# voltagetransfer.net
KiCad netlist of a schematic drawn in EAGLE
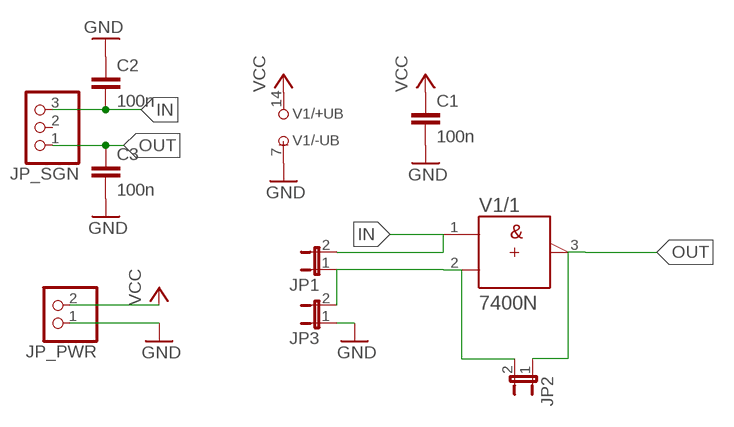
[diagram p0: schematic, sheet 1]

(export (version "E")
  (design (tool "Eeschema 10.0.6"))
  (components
    (comp (ref "C1")
      (value "100n")
      (footprint "eagle-import:C025-024X044")
      (libsource (lib "eagle-import") (part "C-EU025-024X044"))
    )
    (comp (ref "C2")
      (value "100n")
      (footprint "eagle-import:C025-024X044")
      (libsource (lib "eagle-import") (part "C-EU025-024X044"))
    )
    (comp (ref "C3")
      (value "100n")
      (footprint "eagle-import:C025-024X044")
      (libsource (lib "eagle-import") (part "C-EU025-024X044"))
    )
    (comp (ref "JP1")
      (value "JP1E")
      (footprint "eagle-import:JP1")
      (libsource (lib "eagle-import") (part "JP1E"))
    )
    (comp (ref "JP2")
      (value "JP1E")
      (footprint "eagle-import:JP1")
      (libsource (lib "eagle-import") (part "JP1E"))
    )
    (comp (ref "JP3")
      (value "JP1E")
      (footprint "eagle-import:JP1")
      (libsource (lib "eagle-import") (part "JP1E"))
    )
    (comp (ref "JP_PWR")
      (value "PINHD-1X2/90")
      (footprint "eagle-import:1X02_90")
      (libsource (lib "eagle-import") (part "PINHD-1X2/90"))
    )
    (comp (ref "JP_SGN")
      (value "PINHD-1X3/90")
      (footprint "eagle-import:1X03_90")
      (libsource (lib "eagle-import") (part "PINHD-1X3/90"))
    )
    (comp (ref "V1")
      (value "7400N")
      (footprint "eagle-import:DIL14")
      (libsource (lib "eagle-import") (part "7400N"))
    )
  )
  (nets
    (net (code "1") (name "GND") (class "Default")
      (node (ref "C1") (pin "2") (pinfunction "2_2") (pintype "passive"))
      (node (ref "C2") (pin "1") (pinfunction "1_1") (pintype "passive"))
      (node (ref "C3") (pin "2") (pinfunction "2_2") (pintype "passive"))
      (node (ref "JP3") (pin "1") (pinfunction "1_1") (pintype "passive"))
      (node (ref "JP_PWR") (pin "1") (pinfunction "1_1") (pintype "passive"))
      (node (ref "V1") (pin "7") (pinfunction "-UB_7") (pintype "power_in"))
    )
    (net (code "2") (name "IN") (class "Default")
      (node (ref "C2") (pin "2") (pinfunction "2_2") (pintype "passive"))
      (node (ref "JP1") (pin "2") (pinfunction "2_2") (pintype "passive"))
      (node (ref "JP_SGN") (pin "3") (pinfunction "3_3") (pintype "passive"))
      (node (ref "V1") (pin "1") (pinfunction "A_1") (pintype "input"))
    )
    (net (code "3") (name "Net-(V1C-B)") (class "Default")
      (node (ref "JP1") (pin "1") (pinfunction "1_1") (pintype "passive"))
      (node (ref "JP2") (pin "2") (pinfunction "2_2") (pintype "passive"))
      (node (ref "JP3") (pin "2") (pinfunction "2_2") (pintype "passive"))
      (node (ref "V1") (pin "2") (pinfunction "B_2") (pintype "input"))
    )
    (net (code "4") (name "OUT") (class "Default")
      (node (ref "C3") (pin "1") (pinfunction "1_1") (pintype "passive"))
      (node (ref "JP2") (pin "1") (pinfunction "1_1") (pintype "passive"))
      (node (ref "JP_SGN") (pin "1") (pinfunction "1_1") (pintype "passive"))
      (node (ref "V1") (pin "3") (pinfunction "Y_3") (pintype "output"))
    )
    (net (code "5") (name "VCC") (class "Default")
      (node (ref "C1") (pin "1") (pinfunction "1_1") (pintype "passive"))
      (node (ref "JP_PWR") (pin "2") (pinfunction "2_2") (pintype "passive"))
      (node (ref "V1") (pin "14") (pinfunction "+UB_14") (pintype "power_in"))
    )
    (net (code "6") (name "unconnected-(JP_SGN-Pad2)") (class "Default")
      (node (ref "JP_SGN") (pin "2") (pinfunction "2_2") (pintype "passive"))
    )
  )
)
